# remoteserialcontroller.net
KiCad netlist of a schematic drawn in EAGLE
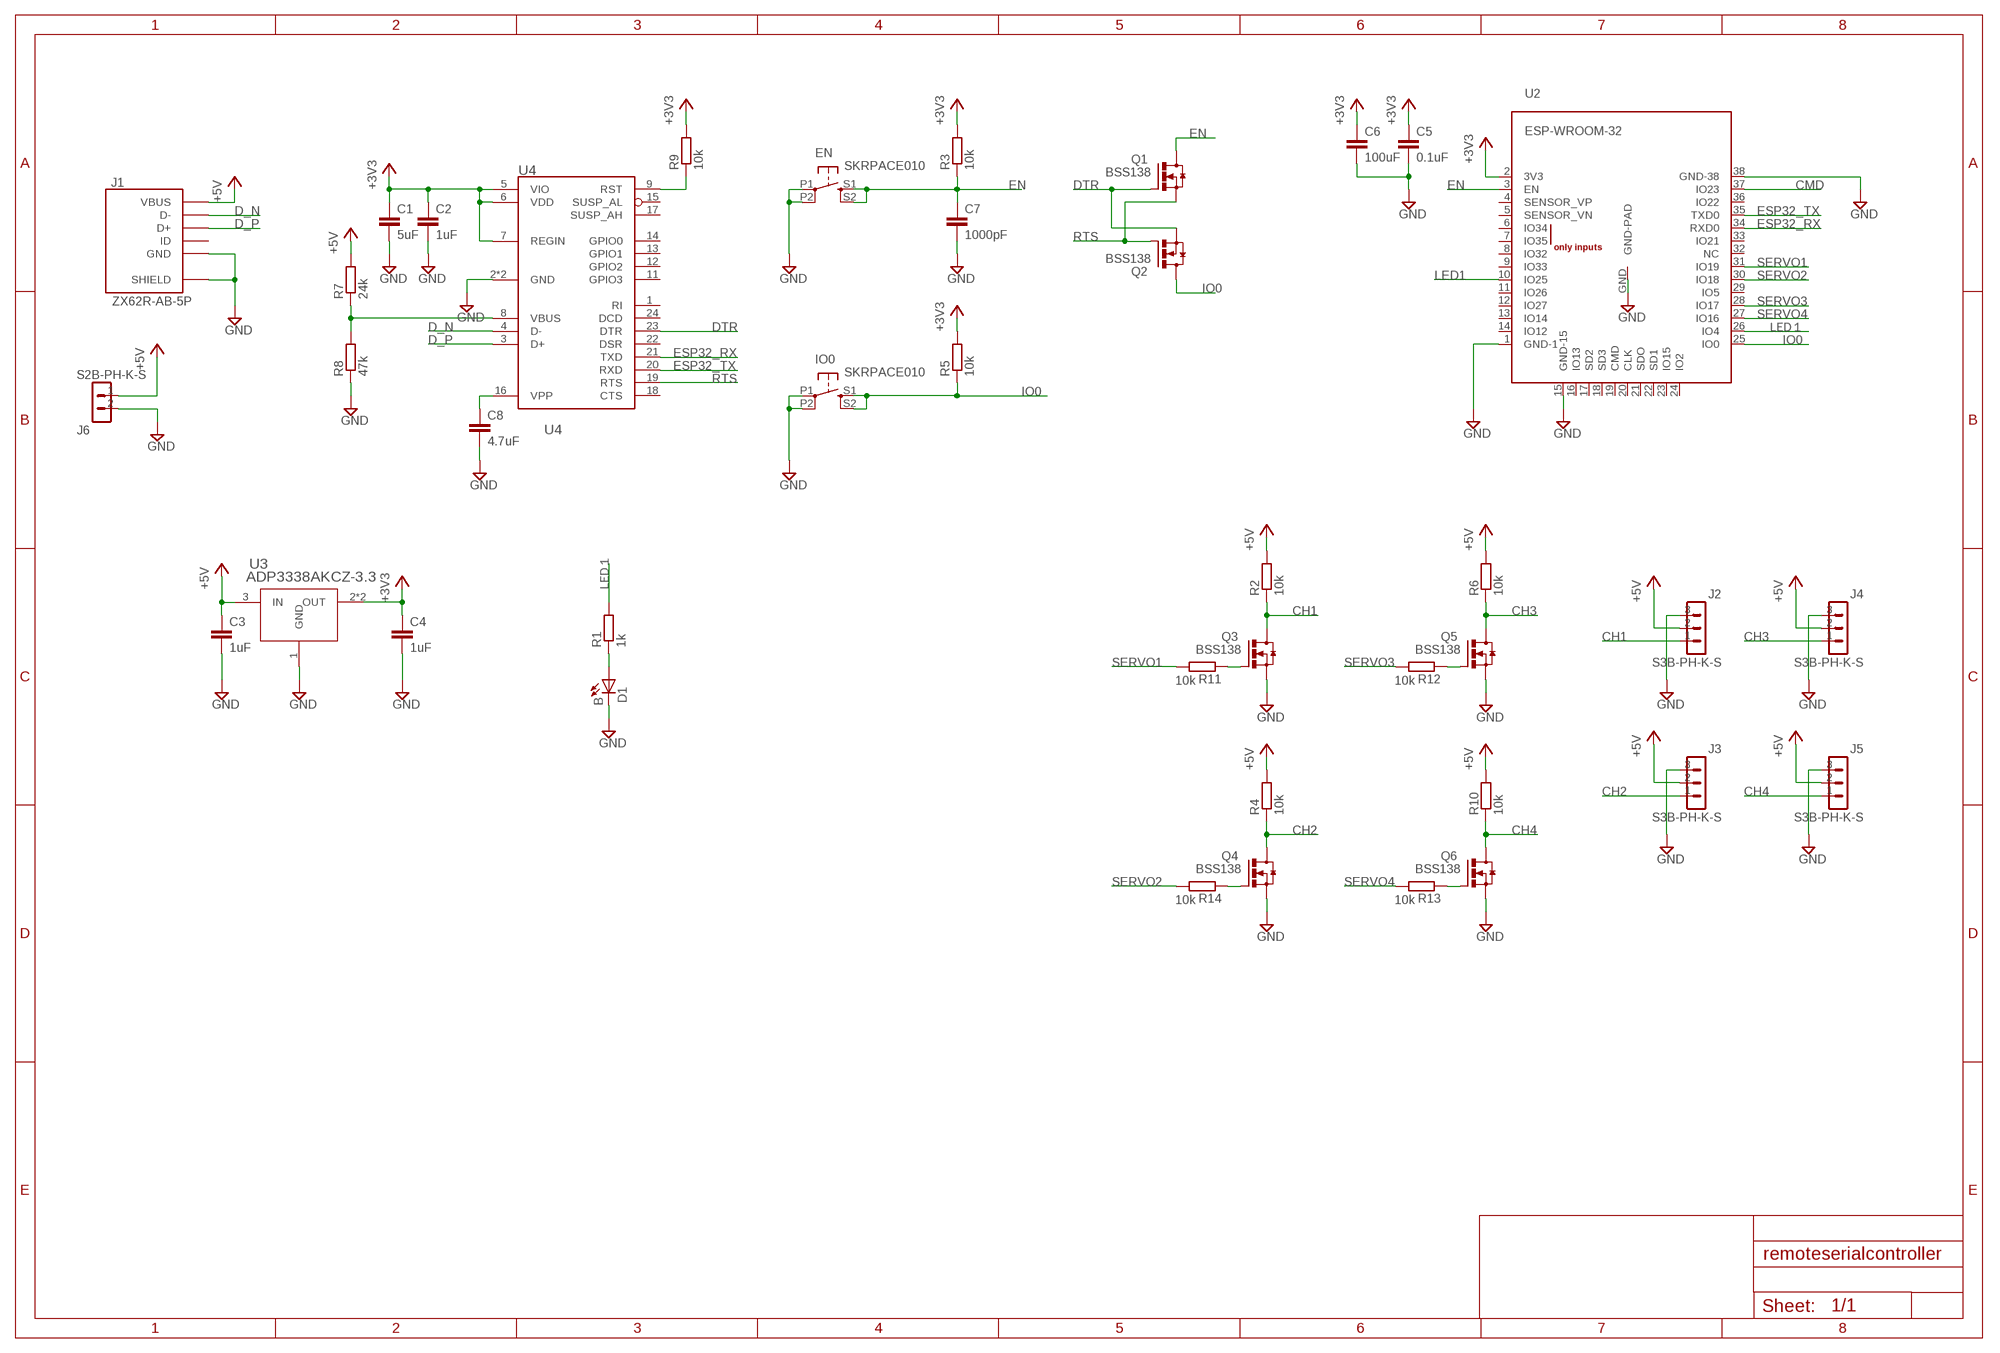
[diagram p0: schematic, sheet 1]

(export (version "E")
  (design (tool "Eeschema 10.0.6"))
  (components
    (comp (ref "C1")
      (value "5uF")
      (footprint "eagle-import:C0603")
      (libsource (lib "eagle-import") (part "C-EUC0603"))
    )
    (comp (ref "C2")
      (value "1uF")
      (footprint "eagle-import:C0603")
      (libsource (lib "eagle-import") (part "C-EUC0603"))
    )
    (comp (ref "C3")
      (value "1uF")
      (footprint "eagle-import:C0603")
      (libsource (lib "eagle-import") (part "C-EUC0603"))
    )
    (comp (ref "C4")
      (value "1uF")
      (footprint "eagle-import:C0603")
      (libsource (lib "eagle-import") (part "C-EUC0603"))
    )
    (comp (ref "C5")
      (value "0.1uF")
      (footprint "eagle-import:C0603")
      (libsource (lib "eagle-import") (part "C-EUC0603"))
    )
    (comp (ref "C6")
      (value "100uF")
      (footprint "eagle-import:C1210")
      (libsource (lib "eagle-import") (part "C-EUC1210"))
    )
    (comp (ref "C7")
      (value "1000pF")
      (footprint "eagle-import:C0603")
      (libsource (lib "eagle-import") (part "C-EUC0603"))
    )
    (comp (ref "C8")
      (value "4.7uF")
      (footprint "eagle-import:C0603")
      (libsource (lib "eagle-import") (part "C-EUC0603"))
    )
    (comp (ref "D1")
      (value "B")
      (footprint "eagle-import:CHIPLED_0603")
      (libsource (lib "eagle-import") (part "LEDCHIPLED_0603"))
    )
    (comp (ref "EN")
      (value "SKRPACE010")
      (footprint "eagle-import:SKRPACE010")
      (libsource (lib "eagle-import") (part "SKRPACE010"))
    )
    (comp (ref "IO0")
      (value "SKRPACE010")
      (footprint "eagle-import:SKRPACE010")
      (libsource (lib "eagle-import") (part "SKRPACE010"))
    )
    (comp (ref "J1")
      (value "ZX62R-AB-5P")
      (footprint "eagle-import:ZX62R-B-5PA")
      (libsource (lib "eagle-import") (part "ZX62R-AB-5P"))
    )
    (comp (ref "J2")
      (value "S3B-PH-K-S")
      (footprint "eagle-import:S3B-PH-K-S")
      (libsource (lib "eagle-import") (part "S3B-PH-K-S"))
    )
    (comp (ref "J3")
      (value "S3B-PH-K-S")
      (footprint "eagle-import:S3B-PH-K-S")
      (libsource (lib "eagle-import") (part "S3B-PH-K-S"))
    )
    (comp (ref "J4")
      (value "S3B-PH-K-S")
      (footprint "eagle-import:S3B-PH-K-S")
      (libsource (lib "eagle-import") (part "S3B-PH-K-S"))
    )
    (comp (ref "J5")
      (value "S3B-PH-K-S")
      (footprint "eagle-import:S3B-PH-K-S")
      (libsource (lib "eagle-import") (part "S3B-PH-K-S"))
    )
    (comp (ref "J6")
      (value "S2B-PH-K-S")
      (footprint "eagle-import:S2B-PH-K-S")
      (libsource (lib "eagle-import") (part "S2B-PH-K-S"))
    )
    (comp (ref "Q1")
      (value "BSS138")
      (footprint "eagle-import:SOT23-N-MOSFET")
      (libsource (lib "eagle-import") (part "BSS138"))
    )
    (comp (ref "Q2")
      (value "BSS138")
      (footprint "eagle-import:SOT23-N-MOSFET")
      (libsource (lib "eagle-import") (part "BSS138"))
    )
    (comp (ref "Q3")
      (value "BSS138")
      (footprint "eagle-import:SOT23-N-MOSFET")
      (libsource (lib "eagle-import") (part "BSS138"))
    )
    (comp (ref "Q4")
      (value "BSS138")
      (footprint "eagle-import:SOT23-N-MOSFET")
      (libsource (lib "eagle-import") (part "BSS138"))
    )
    (comp (ref "Q5")
      (value "BSS138")
      (footprint "eagle-import:SOT23-N-MOSFET")
      (libsource (lib "eagle-import") (part "BSS138"))
    )
    (comp (ref "Q6")
      (value "BSS138")
      (footprint "eagle-import:SOT23-N-MOSFET")
      (libsource (lib "eagle-import") (part "BSS138"))
    )
    (comp (ref "R1")
      (value "1k")
      (footprint "eagle-import:R0603")
      (libsource (lib "eagle-import") (part "R-EU_R0603"))
    )
    (comp (ref "R2")
      (value "10k")
      (footprint "eagle-import:R0603")
      (libsource (lib "eagle-import") (part "R-EU_R0603"))
    )
    (comp (ref "R3")
      (value "10k")
      (footprint "eagle-import:R0603")
      (libsource (lib "eagle-import") (part "R-EU_R0603"))
    )
    (comp (ref "R4")
      (value "10k")
      (footprint "eagle-import:R0603")
      (libsource (lib "eagle-import") (part "R-EU_R0603"))
    )
    (comp (ref "R5")
      (value "10k")
      (footprint "eagle-import:R0603")
      (libsource (lib "eagle-import") (part "R-EU_R0603"))
    )
    (comp (ref "R6")
      (value "10k")
      (footprint "eagle-import:R0603")
      (libsource (lib "eagle-import") (part "R-EU_R0603"))
    )
    (comp (ref "R7")
      (value "24k")
      (footprint "eagle-import:R0603")
      (libsource (lib "eagle-import") (part "R-EU_R0603"))
    )
    (comp (ref "R8")
      (value "47k")
      (footprint "eagle-import:R0603")
      (libsource (lib "eagle-import") (part "R-EU_R0603"))
    )
    (comp (ref "R9")
      (value "10k")
      (footprint "eagle-import:R0603")
      (libsource (lib "eagle-import") (part "R-EU_R0603"))
    )
    (comp (ref "R10")
      (value "10k")
      (footprint "eagle-import:R0603")
      (libsource (lib "eagle-import") (part "R-EU_R0603"))
    )
    (comp (ref "R11")
      (value "10k")
      (footprint "eagle-import:R0603")
      (libsource (lib "eagle-import") (part "R-EU_R0603"))
    )
    (comp (ref "R12")
      (value "10k")
      (footprint "eagle-import:R0603")
      (libsource (lib "eagle-import") (part "R-EU_R0603"))
    )
    (comp (ref "R13")
      (value "10k")
      (footprint "eagle-import:R0603")
      (libsource (lib "eagle-import") (part "R-EU_R0603"))
    )
    (comp (ref "R14")
      (value "10k")
      (footprint "eagle-import:R0603")
      (libsource (lib "eagle-import") (part "R-EU_R0603"))
    )
    (comp (ref "U2")
      (value "ESP-WROOM-32")
      (footprint "eagle-import:ESP-WROOM-32")
      (libsource (lib "eagle-import") (part "ESP-WROOM-32"))
    )
    (comp (ref "U3")
      (value "ADP3338AKCZ-3.3")
      (footprint "eagle-import:SOT233")
      (libsource (lib "eagle-import") (part "ADP3338AKCZ-3.3"))
    )
    (comp (ref "U4")
      (value "CP2104")
      (footprint "eagle-import:QFN24-SILABS")
      (libsource (lib "eagle-import") (part "CP2104"))
    )
  )
  (nets
    (net (code "1") (name "+3V3") (class "Default")
      (node (ref "C1") (pin "1") (pinfunction "1_1") (pintype "passive"))
      (node (ref "C2") (pin "1") (pinfunction "1_1") (pintype "passive"))
      (node (ref "C4") (pin "1") (pinfunction "1_1") (pintype "passive"))
      (node (ref "C5") (pin "1") (pinfunction "1_1") (pintype "passive"))
      (node (ref "C6") (pin "1") (pinfunction "1_1") (pintype "passive"))
      (node (ref "R3") (pin "2") (pinfunction "2_2") (pintype "passive"))
      (node (ref "R5") (pin "2") (pinfunction "2_2") (pintype "passive"))
      (node (ref "R9") (pin "2") (pinfunction "2_2") (pintype "passive"))
      (node (ref "U2") (pin "2") (pinfunction "3V3_2") (pintype "bidirectional"))
      (node (ref "U3") (pin "2") (pinfunction "OUT_2") (pintype "passive"))
      (node (ref "U3") (pin "4") (pinfunction "OUT_4") (pintype "passive"))
      (node (ref "U4") (pin "5") (pinfunction "VIO_5") (pintype "bidirectional"))
      (node (ref "U4") (pin "6") (pinfunction "VDD_6") (pintype "bidirectional"))
      (node (ref "U4") (pin "7") (pinfunction "REGIN_7") (pintype "bidirectional"))
    )
    (net (code "2") (name "+5V") (class "Default")
      (node (ref "C3") (pin "1") (pinfunction "1_1") (pintype "passive"))
      (node (ref "J1") (pin "VCC") (pinfunction "VBUS_VCC") (pintype "bidirectional"))
      (node (ref "J2") (pin "2") (pinfunction "2_2") (pintype "bidirectional"))
      (node (ref "J3") (pin "2") (pinfunction "2_2") (pintype "bidirectional"))
      (node (ref "J4") (pin "2") (pinfunction "2_2") (pintype "bidirectional"))
      (node (ref "J5") (pin "2") (pinfunction "2_2") (pintype "bidirectional"))
      (node (ref "J6") (pin "1") (pinfunction "1_1") (pintype "bidirectional"))
      (node (ref "R10") (pin "2") (pinfunction "2_2") (pintype "passive"))
      (node (ref "R2") (pin "2") (pinfunction "2_2") (pintype "passive"))
      (node (ref "R4") (pin "2") (pinfunction "2_2") (pintype "passive"))
      (node (ref "R6") (pin "2") (pinfunction "2_2") (pintype "passive"))
      (node (ref "R7") (pin "2") (pinfunction "2_2") (pintype "passive"))
      (node (ref "U3") (pin "3") (pinfunction "IN_3") (pintype "passive"))
    )
    (net (code "3") (name "/CH1") (class "Default")
      (node (ref "J2") (pin "1") (pinfunction "1_1") (pintype "bidirectional"))
      (node (ref "Q3") (pin "D") (pinfunction "D_D") (pintype "passive"))
      (node (ref "R2") (pin "1") (pinfunction "1_1") (pintype "passive"))
    )
    (net (code "4") (name "/CH2") (class "Default")
      (node (ref "J3") (pin "1") (pinfunction "1_1") (pintype "bidirectional"))
      (node (ref "Q4") (pin "D") (pinfunction "D_D") (pintype "passive"))
      (node (ref "R4") (pin "1") (pinfunction "1_1") (pintype "passive"))
    )
    (net (code "5") (name "/CH3") (class "Default")
      (node (ref "J4") (pin "1") (pinfunction "1_1") (pintype "bidirectional"))
      (node (ref "Q5") (pin "D") (pinfunction "D_D") (pintype "passive"))
      (node (ref "R6") (pin "1") (pinfunction "1_1") (pintype "passive"))
    )
    (net (code "6") (name "/CH4") (class "Default")
      (node (ref "J5") (pin "1") (pinfunction "1_1") (pintype "bidirectional"))
      (node (ref "Q6") (pin "D") (pinfunction "D_D") (pintype "passive"))
      (node (ref "R10") (pin "1") (pinfunction "1_1") (pintype "passive"))
    )
    (net (code "7") (name "/CMD") (class "Default")
      (node (ref "U2") (pin "37") (pinfunction "IO23_37") (pintype "bidirectional"))
    )
    (net (code "8") (name "/DTR") (class "Default")
      (node (ref "Q1") (pin "G") (pinfunction "G_G") (pintype "passive"))
      (node (ref "Q2") (pin "S") (pinfunction "S_S") (pintype "passive"))
      (node (ref "U4") (pin "23") (pinfunction "DTR_23") (pintype "bidirectional"))
    )
    (net (code "9") (name "/D_N") (class "Default")
      (node (ref "J1") (pin "D-") (pinfunction "D-_D-") (pintype "bidirectional"))
      (node (ref "U4") (pin "4") (pinfunction "D-_4") (pintype "bidirectional"))
    )
    (net (code "10") (name "/D_P") (class "Default")
      (node (ref "J1") (pin "D+") (pinfunction "D+_D+") (pintype "bidirectional"))
      (node (ref "U4") (pin "3") (pinfunction "D+_3") (pintype "bidirectional"))
    )
    (net (code "11") (name "/EN") (class "Default")
      (node (ref "C7") (pin "1") (pinfunction "1_1") (pintype "passive"))
      (node (ref "EN") (pin "S1") (pinfunction "S_S1") (pintype "passive"))
      (node (ref "EN") (pin "S2") (pinfunction "S1_S2") (pintype "passive"))
      (node (ref "Q1") (pin "D") (pinfunction "D_D") (pintype "passive"))
      (node (ref "R3") (pin "1") (pinfunction "1_1") (pintype "passive"))
      (node (ref "U2") (pin "3") (pinfunction "EN_3") (pintype "bidirectional"))
    )
    (net (code "12") (name "/ESP32_RX") (class "Default")
      (node (ref "U2") (pin "34") (pinfunction "RXD0_34") (pintype "bidirectional"))
      (node (ref "U4") (pin "21") (pinfunction "TXD_21") (pintype "bidirectional"))
    )
    (net (code "13") (name "/ESP32_TX") (class "Default")
      (node (ref "U2") (pin "35") (pinfunction "TXD0_35") (pintype "bidirectional"))
      (node (ref "U4") (pin "20") (pinfunction "RXD_20") (pintype "bidirectional"))
    )
    (net (code "14") (name "/IO0") (class "Default")
      (node (ref "IO0") (pin "S1") (pinfunction "S_S1") (pintype "passive"))
      (node (ref "IO0") (pin "S2") (pinfunction "S1_S2") (pintype "passive"))
      (node (ref "Q2") (pin "D") (pinfunction "D_D") (pintype "passive"))
      (node (ref "R5") (pin "1") (pinfunction "1_1") (pintype "passive"))
      (node (ref "U2") (pin "25") (pinfunction "IO0_25") (pintype "bidirectional"))
    )
    (net (code "15") (name "/LED1") (class "Default")
      (node (ref "U2") (pin "10") (pinfunction "IO25_10") (pintype "bidirectional"))
    )
    (net (code "16") (name "/LED１") (class "Default")
      (node (ref "R1") (pin "2") (pinfunction "2_2") (pintype "passive"))
      (node (ref "U2") (pin "26") (pinfunction "IO4_26") (pintype "bidirectional"))
    )
    (net (code "17") (name "/RTS") (class "Default")
      (node (ref "Q1") (pin "S") (pinfunction "S_S") (pintype "passive"))
      (node (ref "Q2") (pin "G") (pinfunction "G_G") (pintype "passive"))
      (node (ref "U4") (pin "19") (pinfunction "RTS_19") (pintype "bidirectional"))
    )
    (net (code "18") (name "/SERVO1") (class "Default")
      (node (ref "R11") (pin "2") (pinfunction "2_2") (pintype "passive"))
      (node (ref "U2") (pin "31") (pinfunction "IO19_31") (pintype "bidirectional"))
    )
    (net (code "19") (name "/SERVO2") (class "Default")
      (node (ref "R14") (pin "2") (pinfunction "2_2") (pintype "passive"))
      (node (ref "U2") (pin "30") (pinfunction "IO18_30") (pintype "bidirectional"))
    )
    (net (code "20") (name "/SERVO3") (class "Default")
      (node (ref "R12") (pin "2") (pinfunction "2_2") (pintype "passive"))
      (node (ref "U2") (pin "28") (pinfunction "IO17_28") (pintype "bidirectional"))
    )
    (net (code "21") (name "/SERVO4") (class "Default")
      (node (ref "R13") (pin "2") (pinfunction "2_2") (pintype "passive"))
      (node (ref "U2") (pin "27") (pinfunction "IO16_27") (pintype "bidirectional"))
    )
    (net (code "22") (name "GND") (class "Default")
      (node (ref "C1") (pin "2") (pinfunction "2_2") (pintype "passive"))
      (node (ref "C2") (pin "2") (pinfunction "2_2") (pintype "passive"))
      (node (ref "C3") (pin "2") (pinfunction "2_2") (pintype "passive"))
      (node (ref "C4") (pin "2") (pinfunction "2_2") (pintype "passive"))
      (node (ref "C5") (pin "2") (pinfunction "2_2") (pintype "passive"))
      (node (ref "C6") (pin "2") (pinfunction "2_2") (pintype "passive"))
      (node (ref "C7") (pin "2") (pinfunction "2_2") (pintype "passive"))
      (node (ref "C8") (pin "2") (pinfunction "2_2") (pintype "passive"))
      (node (ref "D1") (pin "C") (pinfunction "C_C") (pintype "passive"))
      (node (ref "EN") (pin "P1") (pinfunction "P_P1") (pintype "passive"))
      (node (ref "EN") (pin "P2") (pinfunction "P1_P2") (pintype "passive"))
      (node (ref "IO0") (pin "P1") (pinfunction "P_P1") (pintype "passive"))
      (node (ref "IO0") (pin "P2") (pinfunction "P1_P2") (pintype "passive"))
      (node (ref "J1") (pin "GND") (pinfunction "GND_GND") (pintype "bidirectional"))
      (node (ref "J1") (pin "SHIELD@1") (pinfunction "SHIELD_SHIELD@1") (pintype "bidirectional"))
      (node (ref "J1") (pin "SHIELD@2") (pinfunction "SHIELD_SHIELD@2") (pintype "bidirectional"))
      (node (ref "J1") (pin "SHIELD@3") (pinfunction "SHIELD_SHIELD@3") (pintype "bidirectional"))
      (node (ref "J1") (pin "SHIELD@4") (pinfunction "SHIELD_SHIELD@4") (pintype "bidirectional"))
      (node (ref "J2") (pin "3") (pinfunction "3_3") (pintype "bidirectional"))
      (node (ref "J3") (pin "3") (pinfunction "3_3") (pintype "bidirectional"))
      (node (ref "J4") (pin "3") (pinfunction "3_3") (pintype "bidirectional"))
      (node (ref "J5") (pin "3") (pinfunction "3_3") (pintype "bidirectional"))
      (node (ref "J6") (pin "2") (pinfunction "2_2") (pintype "bidirectional"))
      (node (ref "Q3") (pin "S") (pinfunction "S_S") (pintype "passive"))
      (node (ref "Q4") (pin "S") (pinfunction "S_S") (pintype "passive"))
      (node (ref "Q5") (pin "S") (pinfunction "S_S") (pintype "passive"))
      (node (ref "Q6") (pin "S") (pinfunction "S_S") (pintype "passive"))
      (node (ref "R8") (pin "1") (pinfunction "1_1") (pintype "passive"))
      (node (ref "U2") (pin "1") (pinfunction "GND-1_1") (pintype "bidirectional"))
      (node (ref "U2") (pin "15") (pinfunction "GND-15_15") (pintype "bidirectional"))
      (node (ref "U2") (pin "38") (pinfunction "GND-38_38") (pintype "bidirectional"))
      (node (ref "U2") (pin "GND") (pinfunction "GND-PAD_GND") (pintype "bidirectional"))
      (node (ref "U3") (pin "1") (pinfunction "GND_1") (pintype "passive"))
      (node (ref "U4") (pin "2") (pinfunction "GND_2") (pintype "bidirectional"))
      (node (ref "U4") (pin "25") (pinfunction "GND_25") (pintype "bidirectional"))
    )
    (net (code "23") (name "Net-(D1-PadA)") (class "Default")
      (node (ref "D1") (pin "A") (pinfunction "A_A") (pintype "passive"))
      (node (ref "R1") (pin "1") (pinfunction "1_1") (pintype "passive"))
    )
    (net (code "24") (name "Net-(Q3-PadG)") (class "Default")
      (node (ref "Q3") (pin "G") (pinfunction "G_G") (pintype "passive"))
      (node (ref "R11") (pin "1") (pinfunction "1_1") (pintype "passive"))
    )
    (net (code "25") (name "Net-(Q4-PadG)") (class "Default")
      (node (ref "Q4") (pin "G") (pinfunction "G_G") (pintype "passive"))
      (node (ref "R14") (pin "1") (pinfunction "1_1") (pintype "passive"))
    )
    (net (code "26") (name "Net-(Q5-PadG)") (class "Default")
      (node (ref "Q5") (pin "G") (pinfunction "G_G") (pintype "passive"))
      (node (ref "R12") (pin "1") (pinfunction "1_1") (pintype "passive"))
    )
    (net (code "27") (name "Net-(Q6-PadG)") (class "Default")
      (node (ref "Q6") (pin "G") (pinfunction "G_G") (pintype "passive"))
      (node (ref "R13") (pin "1") (pinfunction "1_1") (pintype "passive"))
    )
    (net (code "28") (name "Net-(U4-RST)") (class "Default")
      (node (ref "R9") (pin "1") (pinfunction "1_1") (pintype "passive"))
      (node (ref "U4") (pin "9") (pinfunction "RST_9") (pintype "bidirectional"))
    )
    (net (code "29") (name "Net-(U4-VBUS)") (class "Default")
      (node (ref "R7") (pin "1") (pinfunction "1_1") (pintype "passive"))
      (node (ref "R8") (pin "2") (pinfunction "2_2") (pintype "passive"))
      (node (ref "U4") (pin "8") (pinfunction "VBUS_8") (pintype "bidirectional"))
    )
    (net (code "30") (name "Net-(U4-VPP)") (class "Default")
      (node (ref "C8") (pin "1") (pinfunction "1_1") (pintype "passive"))
      (node (ref "U4") (pin "16") (pinfunction "VPP_16") (pintype "bidirectional"))
    )
    (net (code "31") (name "unconnected-(J1-PadID)") (class "Default")
      (node (ref "J1") (pin "ID") (pinfunction "ID_ID") (pintype "bidirectional"))
    )
    (net (code "32") (name "unconnected-(U2-CLK-Pad20)") (class "Default")
      (node (ref "U2") (pin "20") (pinfunction "CLK_20") (pintype "bidirectional"))
    )
    (net (code "33") (name "unconnected-(U2-CMD-Pad19)") (class "Default")
      (node (ref "U2") (pin "19") (pinfunction "CMD_19") (pintype "bidirectional"))
    )
    (net (code "34") (name "unconnected-(U2-IO2-Pad24)") (class "Default")
      (node (ref "U2") (pin "24") (pinfunction "IO2_24") (pintype "bidirectional"))
    )
    (net (code "35") (name "unconnected-(U2-IO5-Pad29)") (class "Default")
      (node (ref "U2") (pin "29") (pinfunction "IO5_29") (pintype "bidirectional"))
    )
    (net (code "36") (name "unconnected-(U2-IO12-Pad14)") (class "Default")
      (node (ref "U2") (pin "14") (pinfunction "IO12_14") (pintype "bidirectional"))
    )
    (net (code "37") (name "unconnected-(U2-IO13-Pad16)") (class "Default")
      (node (ref "U2") (pin "16") (pinfunction "IO13_16") (pintype "bidirectional"))
    )
    (net (code "38") (name "unconnected-(U2-IO14-Pad13)") (class "Default")
      (node (ref "U2") (pin "13") (pinfunction "IO14_13") (pintype "bidirectional"))
    )
    (net (code "39") (name "unconnected-(U2-IO15-Pad23)") (class "Default")
      (node (ref "U2") (pin "23") (pinfunction "IO15_23") (pintype "bidirectional"))
    )
    (net (code "40") (name "unconnected-(U2-IO21-Pad33)") (class "Default")
      (node (ref "U2") (pin "33") (pinfunction "IO21_33") (pintype "bidirectional"))
    )
    (net (code "41") (name "unconnected-(U2-IO22-Pad36)") (class "Default")
      (node (ref "U2") (pin "36") (pinfunction "IO22_36") (pintype "bidirectional"))
    )
    (net (code "42") (name "unconnected-(U2-IO26-Pad11)") (class "Default")
      (node (ref "U2") (pin "11") (pinfunction "IO26_11") (pintype "bidirectional"))
    )
    (net (code "43") (name "unconnected-(U2-IO27-Pad12)") (class "Default")
      (node (ref "U2") (pin "12") (pinfunction "IO27_12") (pintype "bidirectional"))
    )
    (net (code "44") (name "unconnected-(U2-IO32-Pad8)") (class "Default")
      (node (ref "U2") (pin "8") (pinfunction "IO32_8") (pintype "bidirectional"))
    )
    (net (code "45") (name "unconnected-(U2-IO33-Pad9)") (class "Default")
      (node (ref "U2") (pin "9") (pinfunction "IO33_9") (pintype "bidirectional"))
    )
    (net (code "46") (name "unconnected-(U2-IO34-Pad6)") (class "Default")
      (node (ref "U2") (pin "6") (pinfunction "IO34_6") (pintype "input"))
    )
    (net (code "47") (name "unconnected-(U2-IO35-Pad7)") (class "Default")
      (node (ref "U2") (pin "7") (pinfunction "IO35_7") (pintype "input"))
    )
    (net (code "48") (name "unconnected-(U2-NC-Pad32)") (class "Default")
      (node (ref "U2") (pin "32") (pinfunction "NC_32") (pintype "bidirectional"))
    )
    (net (code "49") (name "unconnected-(U2-SD1-Pad22)") (class "Default")
      (node (ref "U2") (pin "22") (pinfunction "SD1_22") (pintype "bidirectional"))
    )
    (net (code "50") (name "unconnected-(U2-SD2-Pad17)") (class "Default")
      (node (ref "U2") (pin "17") (pinfunction "SD2_17") (pintype "bidirectional"))
    )
    (net (code "51") (name "unconnected-(U2-SD3-Pad18)") (class "Default")
      (node (ref "U2") (pin "18") (pinfunction "SD3_18") (pintype "bidirectional"))
    )
    (net (code "52") (name "unconnected-(U2-SDO-Pad21)") (class "Default")
      (node (ref "U2") (pin "21") (pinfunction "SDO_21") (pintype "bidirectional"))
    )
    (net (code "53") (name "unconnected-(U2-SENSOR_VN-Pad5)") (class "Default")
      (node (ref "U2") (pin "5") (pinfunction "SENSOR_VN_5") (pintype "input"))
    )
    (net (code "54") (name "unconnected-(U2-SENSOR_VP-Pad4)") (class "Default")
      (node (ref "U2") (pin "4") (pinfunction "SENSOR_VP_4") (pintype "input"))
    )
    (net (code "55") (name "unconnected-(U4-CTS-Pad18)") (class "Default")
      (node (ref "U4") (pin "18") (pinfunction "CTS_18") (pintype "bidirectional"))
    )
    (net (code "56") (name "unconnected-(U4-DCD-Pad24)") (class "Default")
      (node (ref "U4") (pin "24") (pinfunction "DCD_24") (pintype "bidirectional"))
    )
    (net (code "57") (name "unconnected-(U4-DSR-Pad22)") (class "Default")
      (node (ref "U4") (pin "22") (pinfunction "DSR_22") (pintype "bidirectional"))
    )
    (net (code "58") (name "unconnected-(U4-GPIO0-Pad14)") (class "Default")
      (node (ref "U4") (pin "14") (pinfunction "GPIO0_14") (pintype "bidirectional"))
    )
    (net (code "59") (name "unconnected-(U4-GPIO1-Pad13)") (class "Default")
      (node (ref "U4") (pin "13") (pinfunction "GPIO1_13") (pintype "bidirectional"))
    )
    (net (code "60") (name "unconnected-(U4-GPIO2-Pad12)") (class "Default")
      (node (ref "U4") (pin "12") (pinfunction "GPIO2_12") (pintype "bidirectional"))
    )
    (net (code "61") (name "unconnected-(U4-GPIO3-Pad11)") (class "Default")
      (node (ref "U4") (pin "11") (pinfunction "GPIO3_11") (pintype "bidirectional"))
    )
    (net (code "62") (name "unconnected-(U4-RI-Pad1)") (class "Default")
      (node (ref "U4") (pin "1") (pinfunction "RI_1") (pintype "bidirectional"))
    )
    (net (code "63") (name "unconnected-(U4-SUSP_AH-Pad17)") (class "Default")
      (node (ref "U4") (pin "17") (pinfunction "SUSP_AH_17") (pintype "output"))
    )
    (net (code "64") (name "unconnected-(U4-SUSP_AL-Pad15)") (class "Default")
      (node (ref "U4") (pin "15") (pinfunction "SUSP_AL_15") (pintype "bidirectional"))
    )
  )
)
